# Sivasankar_s_Hackpad.net
KiCad netlist of a schematic drawn in EasyEDA Pro
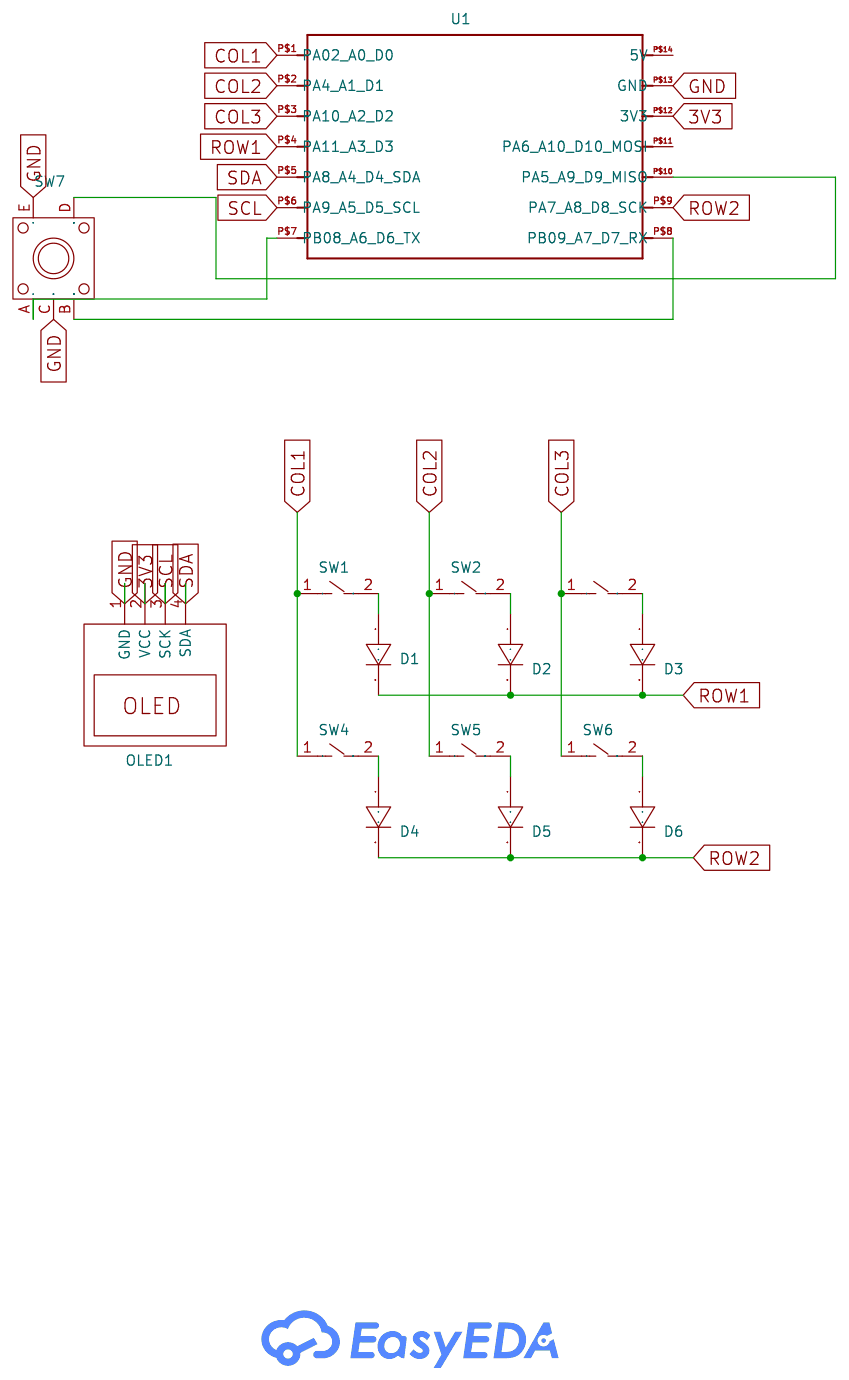
[diagram p0: schematic sheet]

(export (version "E")
  (design (tool "Eeschema 10.0.6"))
  (components
    (comp (ref "D1")
      (value "1N4148")
      (footprint "easyedapro:DO-35_BD2.0-L4.0-P8.00-D0.5-FD")
      (fields (field (name "Manufacturer") "onsemi(安森美)"))
      (libsource (lib "easyedapro") (part "1N4148_C258182"))
    )
    (comp (ref "D2")
      (value "1N4148")
      (footprint "easyedapro:DO-35_BD2.0-L4.0-P8.00-D0.5-FD")
      (fields (field (name "Manufacturer") "onsemi(安森美)"))
      (libsource (lib "easyedapro") (part "1N4148_C258182"))
    )
    (comp (ref "D3")
      (value "1N4148")
      (footprint "easyedapro:DO-35_BD2.0-L4.0-P8.00-D0.5-FD")
      (fields (field (name "Manufacturer") "onsemi(安森美)"))
      (libsource (lib "easyedapro") (part "1N4148_C258182"))
    )
    (comp (ref "D4")
      (value "1N4148")
      (footprint "easyedapro:DO-35_BD2.0-L4.0-P8.00-D0.5-FD")
      (fields (field (name "Manufacturer") "onsemi(安森美)"))
      (libsource (lib "easyedapro") (part "1N4148_C258182"))
    )
    (comp (ref "D5")
      (value "1N4148")
      (footprint "easyedapro:DO-35_BD2.0-L4.0-P8.00-D0.5-FD")
      (fields (field (name "Manufacturer") "onsemi(安森美)"))
      (libsource (lib "easyedapro") (part "1N4148_C258182"))
    )
    (comp (ref "D6")
      (value "1N4148")
      (footprint "easyedapro:DO-35_BD2.0-L4.0-P8.00-D0.5-FD")
      (fields (field (name "Manufacturer") "onsemi(安森美)"))
      (libsource (lib "easyedapro") (part "1N4148_C258182"))
    )
    (comp (ref "OLED1")
      (value "OLED 0.91")
      (footprint "easyedapro:I2C OLED 0.91")
      (fields (field (name "Manufacturer Part") "SSD1306 I2C OLED"))
      (libsource (lib "easyedapro") (part "OLED 0.91"))
    )
    (comp (ref "SW1")
      (value "MX1A-E1NW")
      (footprint "easyedapro:SW-TH_MX1A-E1NW")
      (fields (field (name "Manufacturer") "CHERRY"))
      (libsource (lib "easyedapro") (part "MX1A-E1NW"))
    )
    (comp (ref "SW2")
      (value "MX1A-E1NW")
      (footprint "easyedapro:SW-TH_MX1A-E1NW")
      (fields (field (name "Manufacturer") "CHERRY"))
      (libsource (lib "easyedapro") (part "MX1A-E1NW"))
    )
    (comp (ref "SW3")
      (value "MX1A-E1NW")
      (footprint "easyedapro:SW-TH_MX1A-E1NW")
      (fields (field (name "Manufacturer") "CHERRY"))
      (libsource (lib "easyedapro") (part "MX1A-E1NW"))
    )
    (comp (ref "SW4")
      (value "MX1A-E1NW")
      (footprint "easyedapro:SW-TH_MX1A-E1NW")
      (fields (field (name "Manufacturer") "CHERRY"))
      (libsource (lib "easyedapro") (part "MX1A-E1NW"))
    )
    (comp (ref "SW5")
      (value "MX1A-E1NW")
      (footprint "easyedapro:SW-TH_MX1A-E1NW")
      (fields (field (name "Manufacturer") "CHERRY"))
      (libsource (lib "easyedapro") (part "MX1A-E1NW"))
    )
    (comp (ref "SW6")
      (value "MX1A-E1NW")
      (footprint "easyedapro:SW-TH_MX1A-E1NW")
      (fields (field (name "Manufacturer") "CHERRY"))
      (libsource (lib "easyedapro") (part "MX1A-E1NW"))
    )
    (comp (ref "SW7")
      (value "EC11")
      (footprint "easyedapro:SW-TH_EC111XXXX")
      (fields (field (name "Manufacturer Part") "EC1110120005") (field (name "Manufacturer") "ALPS Electric"))
      (libsource (lib "easyedapro") (part "EC11"))
    )
    (comp (ref "U1")
      (value "XIAO_RP2040_XIAO_RP2040_THROUGH_HOLE")
      (footprint "easyedapro:XIAO_THROUGH_HOLE")
      (libsource (lib "easyedapro") (part "XIAO_RP2040_XIAO_RP2040_THROUGH_HOLE"))
    )
  )
  (nets
    (net (code "1") (name "3V3") (class "Default")
      (node (ref "OLED1") (pin "2") (pinfunction "VCC_2") (pintype "unspecified"))
      (node (ref "U1") (pin "P$12") (pinfunction "3V3_P$12") (pintype "bidirectional"))
    )
    (net (code "2") (name "COL1") (class "Default")
      (node (ref "SW1") (pin "1") (pinfunction "1_1") (pintype "unspecified"))
      (node (ref "SW4") (pin "1") (pinfunction "1_1") (pintype "unspecified"))
      (node (ref "U1") (pin "P$1") (pinfunction "PA02_A0_D0_P$1") (pintype "bidirectional"))
    )
    (net (code "3") (name "COL2") (class "Default")
      (node (ref "SW2") (pin "1") (pinfunction "1_1") (pintype "unspecified"))
      (node (ref "SW5") (pin "1") (pinfunction "1_1") (pintype "unspecified"))
      (node (ref "U1") (pin "P$2") (pinfunction "PA4_A1_D1_P$2") (pintype "bidirectional"))
    )
    (net (code "4") (name "COL3") (class "Default")
      (node (ref "SW3") (pin "1") (pinfunction "1_1") (pintype "unspecified"))
      (node (ref "SW6") (pin "1") (pinfunction "1_1") (pintype "unspecified"))
      (node (ref "U1") (pin "P$3") (pinfunction "PA10_A2_D2_P$3") (pintype "bidirectional"))
    )
    (net (code "5") (name "GND") (class "Default")
      (node (ref "OLED1") (pin "1") (pinfunction "GND_1") (pintype "unspecified"))
      (node (ref "SW7") (pin "C") (pinfunction "C_C") (pintype "unspecified"))
      (node (ref "SW7") (pin "E") (pinfunction "E_E") (pintype "unspecified"))
      (node (ref "U1") (pin "P$13") (pinfunction "GND_P$13") (pintype "bidirectional"))
    )
    (net (code "6") (name "Net-(D1-A)") (class "Default")
      (node (ref "D1") (pin "1") (pinfunction "A_1") (pintype "input"))
      (node (ref "SW1") (pin "2") (pinfunction "2_2") (pintype "unspecified"))
    )
    (net (code "7") (name "Net-(D2-A)") (class "Default")
      (node (ref "D2") (pin "1") (pinfunction "A_1") (pintype "input"))
      (node (ref "SW2") (pin "2") (pinfunction "2_2") (pintype "unspecified"))
    )
    (net (code "8") (name "Net-(D3-A)") (class "Default")
      (node (ref "D3") (pin "1") (pinfunction "A_1") (pintype "input"))
      (node (ref "SW3") (pin "2") (pinfunction "2_2") (pintype "unspecified"))
    )
    (net (code "9") (name "Net-(D4-A)") (class "Default")
      (node (ref "D4") (pin "1") (pinfunction "A_1") (pintype "input"))
      (node (ref "SW4") (pin "2") (pinfunction "2_2") (pintype "unspecified"))
    )
    (net (code "10") (name "Net-(D5-A)") (class "Default")
      (node (ref "D5") (pin "1") (pinfunction "A_1") (pintype "input"))
      (node (ref "SW5") (pin "2") (pinfunction "2_2") (pintype "unspecified"))
    )
    (net (code "11") (name "Net-(D6-A)") (class "Default")
      (node (ref "D6") (pin "1") (pinfunction "A_1") (pintype "input"))
      (node (ref "SW6") (pin "2") (pinfunction "2_2") (pintype "unspecified"))
    )
    (net (code "12") (name "Net-(U1-PA5_A9_D9_MISO)") (class "Default")
      (node (ref "SW7") (pin "D") (pinfunction "D_D") (pintype "unspecified"))
      (node (ref "U1") (pin "P$10") (pinfunction "PA5_A9_D9_MISO_P$10") (pintype "bidirectional"))
    )
    (net (code "13") (name "Net-(U1-PB08_A6_D6_TX)") (class "Default")
      (node (ref "SW7") (pin "A") (pinfunction "A_A") (pintype "unspecified"))
      (node (ref "U1") (pin "P$7") (pinfunction "PB08_A6_D6_TX_P$7") (pintype "bidirectional"))
    )
    (net (code "14") (name "Net-(U1-PB09_A7_D7_RX)") (class "Default")
      (node (ref "SW7") (pin "B") (pinfunction "B_B") (pintype "unspecified"))
      (node (ref "U1") (pin "P$8") (pinfunction "PB09_A7_D7_RX_P$8") (pintype "bidirectional"))
    )
    (net (code "15") (name "ROW1") (class "Default")
      (node (ref "D1") (pin "2") (pinfunction "K_2") (pintype "input"))
      (node (ref "D2") (pin "2") (pinfunction "K_2") (pintype "input"))
      (node (ref "D3") (pin "2") (pinfunction "K_2") (pintype "input"))
      (node (ref "U1") (pin "P$4") (pinfunction "PA11_A3_D3_P$4") (pintype "bidirectional"))
    )
    (net (code "16") (name "ROW2") (class "Default")
      (node (ref "D4") (pin "2") (pinfunction "K_2") (pintype "input"))
      (node (ref "D5") (pin "2") (pinfunction "K_2") (pintype "input"))
      (node (ref "D6") (pin "2") (pinfunction "K_2") (pintype "input"))
      (node (ref "U1") (pin "P$9") (pinfunction "PA7_A8_D8_SCK_P$9") (pintype "bidirectional"))
    )
    (net (code "17") (name "SCL") (class "Default")
      (node (ref "OLED1") (pin "3") (pinfunction "SCK_3") (pintype "unspecified"))
      (node (ref "U1") (pin "P$6") (pinfunction "PA9_A5_D5_SCL_P$6") (pintype "bidirectional"))
    )
    (net (code "18") (name "SDA") (class "Default")
      (node (ref "OLED1") (pin "4") (pinfunction "SDA_4") (pintype "unspecified"))
      (node (ref "U1") (pin "P$5") (pinfunction "PA8_A4_D4_SDA_P$5") (pintype "bidirectional"))
    )
    (net (code "19") (name "unconnected-(U1-5V-PadP$14)") (class "Default")
      (node (ref "U1") (pin "P$14") (pinfunction "5V_P$14") (pintype "bidirectional"))
    )
    (net (code "20") (name "unconnected-(U1-PA6_A10_D10_MOSI-PadP$11)") (class "Default")
      (node (ref "U1") (pin "P$11") (pinfunction "PA6_A10_D10_MOSI_P$11") (pintype "bidirectional"))
    )
  )
)
